# aufsatz_v2_2_dmx.net
KiCad netlist of a schematic drawn in EAGLE
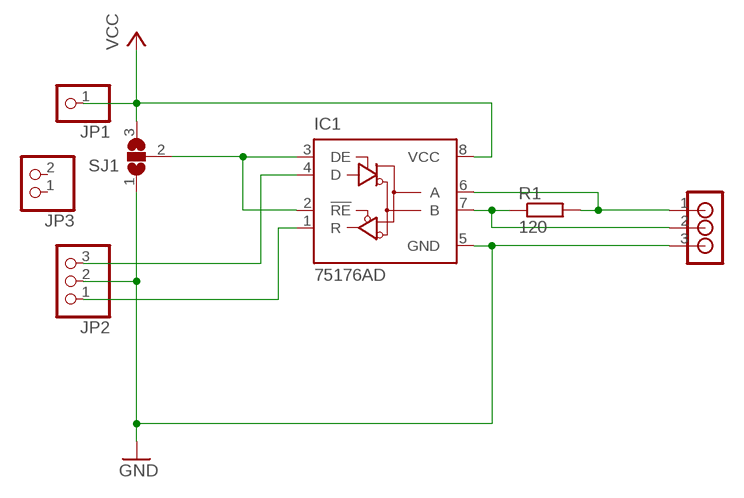
[diagram p0: schematic, sheet 1]

(export (version "E")
  (design (tool "Eeschema 10.0.6"))
  (components
    (comp (ref "IC1")
      (value "75176AD")
      (footprint "eagle-import:D_R-PDSO-G8")
      (libsource (lib "eagle-import") (part "75176AD"))
    )
    (comp (ref "JP1")
      (value "PINHD-1X1")
      (footprint "eagle-import:1X01")
      (libsource (lib "eagle-import") (part "PINHD-1X1"))
    )
    (comp (ref "JP2")
      (value "PINHD-1X3")
      (footprint "eagle-import:1X03")
      (libsource (lib "eagle-import") (part "PINHD-1X3"))
    )
    (comp (ref "JP3")
      (value "PINHD-1X2")
      (footprint "eagle-import:1X02")
      (libsource (lib "eagle-import") (part "PINHD-1X2"))
    )
    (comp (ref "R1")
      (value "120")
      (footprint "eagle-import:R0805")
      (libsource (lib "eagle-import") (part "R-EU_R0805"))
    )
    (comp (ref "SJ1")
      (value "SJ2W")
      (footprint "eagle-import:SJ_2")
      (libsource (lib "eagle-import") (part "SJ2W"))
    )
    (comp (ref "U$1")
      (value "RIACON_59_3")
      (footprint "eagle-import:RIACON_59_3")
      (libsource (lib "eagle-import") (part "RIACON_59_3"))
    )
  )
  (nets
    (net (code "1") (name "GND") (class "Default")
      (node (ref "IC1") (pin "5") (pinfunction "GND_5") (pintype "power_in"))
      (node (ref "JP2") (pin "2") (pinfunction "2_2") (pintype "passive"))
      (node (ref "SJ1") (pin "1") (pinfunction "1_1") (pintype "passive"))
      (node (ref "U$1") (pin "3") (pinfunction "3_3") (pintype "passive"))
    )
    (net (code "2") (name "Net-(IC1-A)") (class "Default")
      (node (ref "IC1") (pin "6") (pinfunction "A_6") (pintype "output"))
      (node (ref "R1") (pin "2") (pinfunction "2_2") (pintype "passive"))
      (node (ref "U$1") (pin "1") (pinfunction "1_1") (pintype "passive"))
    )
    (net (code "3") (name "Net-(IC1-B)") (class "Default")
      (node (ref "IC1") (pin "7") (pinfunction "B_7") (pintype "output"))
      (node (ref "R1") (pin "1") (pinfunction "1_1") (pintype "passive"))
      (node (ref "U$1") (pin "2") (pinfunction "2_2") (pintype "passive"))
    )
    (net (code "4") (name "Net-(IC1-D)") (class "Default")
      (node (ref "IC1") (pin "4") (pinfunction "D_4") (pintype "input"))
      (node (ref "JP2") (pin "3") (pinfunction "3_3") (pintype "passive"))
    )
    (net (code "5") (name "Net-(IC1-DE)") (class "Default")
      (node (ref "IC1") (pin "2") (pinfunction "~{RE}_2") (pintype "input"))
      (node (ref "IC1") (pin "3") (pinfunction "DE_3") (pintype "input"))
      (node (ref "SJ1") (pin "2") (pinfunction "2_2") (pintype "passive"))
    )
    (net (code "6") (name "Net-(IC1-R)") (class "Default")
      (node (ref "IC1") (pin "1") (pinfunction "R_1") (pintype "input"))
      (node (ref "JP2") (pin "1") (pinfunction "1_1") (pintype "passive"))
    )
    (net (code "7") (name "VCC") (class "Default")
      (node (ref "IC1") (pin "8") (pinfunction "VCC_8") (pintype "power_in"))
      (node (ref "JP1") (pin "1") (pinfunction "1_1") (pintype "passive"))
      (node (ref "SJ1") (pin "3") (pinfunction "3_3") (pintype "passive"))
    )
    (net (code "8") (name "unconnected-(JP3-Pad1)") (class "Default")
      (node (ref "JP3") (pin "1") (pinfunction "1_1") (pintype "passive"))
    )
    (net (code "9") (name "unconnected-(JP3-Pad2)") (class "Default")
      (node (ref "JP3") (pin "2") (pinfunction "2_2") (pintype "passive"))
    )
  )
)
